# 4_waffling60-SE_periferals.net
KiCad netlist of a schematic drawn in Altium Designer
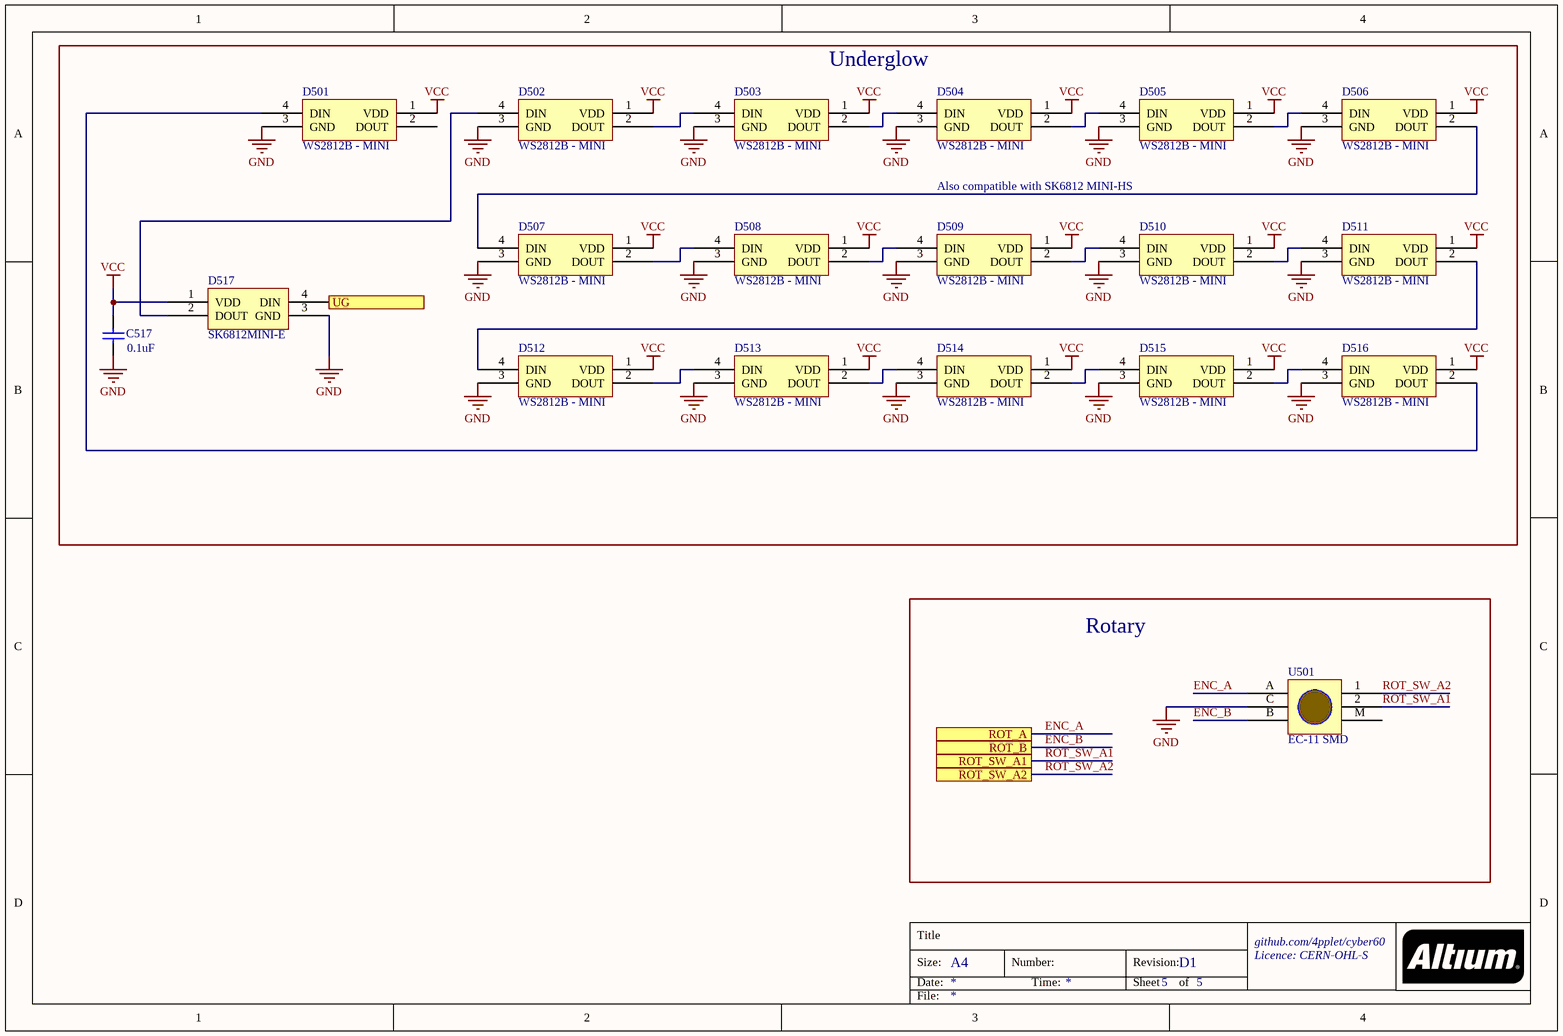
[diagram p0: 4_waffling60-SE_periferals.SchDoc]

(export (version "E")
  (design (tool "Eeschema 10.0.6"))
  (components
    (comp (ref "C517")
      (value "0.1uF")
      (footprint "C0603[1608]")
      (description "Capacitor")
      (fields (field (name "LCSC PART #") "C14663") (field (name "MRF.PART") "CC0603KRX7R9BB104"))
      (libsource (lib "Miscellaneous Devices") (part "Cap"))
    )
    (comp (ref "D501")
      (value "WS2812B - MINI")
      (footprint "WS2812B - 2020")
      (fields (field (name "LCSC PART #") "C965556") (field (name "MRF.PART") "WS2812C-2020"))
      (libsource (lib "Keebs") (part "WS2812B"))
    )
    (comp (ref "D502")
      (value "WS2812B - MINI")
      (footprint "WS2812B - 2020")
      (fields (field (name "LCSC PART #") "C965556") (field (name "MRF.PART") "WS2812C-2020"))
      (libsource (lib "Keebs") (part "WS2812B"))
    )
    (comp (ref "D503")
      (value "WS2812B - MINI")
      (footprint "WS2812B - 2020")
      (fields (field (name "LCSC PART #") "C965556") (field (name "MRF.PART") "WS2812C-2020"))
      (libsource (lib "Keebs") (part "WS2812B"))
    )
    (comp (ref "D504")
      (value "WS2812B - MINI")
      (footprint "WS2812B - 2020")
      (fields (field (name "LCSC PART #") "C965556") (field (name "MRF.PART") "WS2812C-2020"))
      (libsource (lib "Keebs") (part "WS2812B"))
    )
    (comp (ref "D505")
      (value "WS2812B - MINI")
      (footprint "WS2812B - 2020")
      (fields (field (name "LCSC PART #") "C965556") (field (name "MRF.PART") "WS2812C-2020"))
      (libsource (lib "Keebs") (part "WS2812B"))
    )
    (comp (ref "D506")
      (value "WS2812B - MINI")
      (footprint "WS2812B - 2020")
      (fields (field (name "LCSC PART #") "C965556") (field (name "MRF.PART") "WS2812C-2020"))
      (libsource (lib "Keebs") (part "WS2812B"))
    )
    (comp (ref "D507")
      (value "WS2812B - MINI")
      (footprint "WS2812B - 2020")
      (fields (field (name "LCSC PART #") "C965556") (field (name "MRF.PART") "WS2812C-2020"))
      (libsource (lib "Keebs") (part "WS2812B"))
    )
    (comp (ref "D508")
      (value "WS2812B - MINI")
      (footprint "WS2812B - 2020")
      (fields (field (name "LCSC PART #") "C965556") (field (name "MRF.PART") "WS2812C-2020"))
      (libsource (lib "Keebs") (part "WS2812B"))
    )
    (comp (ref "D509")
      (value "WS2812B - MINI")
      (footprint "WS2812B - 2020")
      (fields (field (name "LCSC PART #") "C965556") (field (name "MRF.PART") "WS2812C-2020"))
      (libsource (lib "Keebs") (part "WS2812B"))
    )
    (comp (ref "D510")
      (value "WS2812B - MINI")
      (footprint "WS2812B - 2020")
      (fields (field (name "LCSC PART #") "C965556") (field (name "MRF.PART") "WS2812C-2020"))
      (libsource (lib "Keebs") (part "WS2812B"))
    )
    (comp (ref "D511")
      (value "WS2812B - MINI")
      (footprint "WS2812B - 2020")
      (fields (field (name "LCSC PART #") "C965556") (field (name "MRF.PART") "WS2812C-2020"))
      (libsource (lib "Keebs") (part "WS2812B"))
    )
    (comp (ref "D512")
      (value "WS2812B - MINI")
      (footprint "WS2812B - 2020")
      (fields (field (name "LCSC PART #") "C965556") (field (name "MRF.PART") "WS2812C-2020"))
      (libsource (lib "Keebs") (part "WS2812B"))
    )
    (comp (ref "D513")
      (value "WS2812B - MINI")
      (footprint "WS2812B - 2020")
      (fields (field (name "LCSC PART #") "C965556") (field (name "MRF.PART") "WS2812C-2020"))
      (libsource (lib "Keebs") (part "WS2812B"))
    )
    (comp (ref "D514")
      (value "WS2812B - MINI")
      (footprint "WS2812B - 2020")
      (fields (field (name "LCSC PART #") "C965556") (field (name "MRF.PART") "WS2812C-2020"))
      (libsource (lib "Keebs") (part "WS2812B"))
    )
    (comp (ref "D515")
      (value "WS2812B - MINI")
      (footprint "WS2812B - 2020")
      (fields (field (name "LCSC PART #") "C965556") (field (name "MRF.PART") "WS2812C-2020"))
      (libsource (lib "Keebs") (part "WS2812B"))
    )
    (comp (ref "D516")
      (value "WS2812B - MINI")
      (footprint "WS2812B - 2020")
      (fields (field (name "LCSC PART #") "C965556") (field (name "MRF.PART") "WS2812C-2020"))
      (libsource (lib "Keebs") (part "WS2812B"))
    )
    (comp (ref "D517")
      (value "SK6812MINI-E")
      (footprint "SK6812MINI-E - shaped")
      (fields (field (name "LCSC PART #") "C524051") (field (name "MRF.PART") "DY-S352818/RGBC/6812-2T"))
      (libsource (lib "Keebs") (part "SK6812MINI-E"))
    )
    (comp (ref "U501") (value "EC-11 SMD") (footprint "EC11-SMD") (libsource (lib "Keebs") (part "EC-11")))
  )
  (nets
    (net (code "1") (name "/ENC_A") (class "Default")
      (node (ref "U501") (pin "A") (pinfunction "B_A") (pintype "passive"))
    )
    (net (code "2") (name "/ENC_B") (class "Default")
      (node (ref "U501") (pin "B") (pinfunction "B_B") (pintype "passive"))
    )
    (net (code "3") (name "/ROT_SW_A1") (class "Default")
      (node (ref "U501") (pin "2") (pinfunction "2_2") (pintype "passive"))
    )
    (net (code "4") (name "/ROT_SW_A2") (class "Default")
      (node (ref "U501") (pin "1") (pinfunction "1_1") (pintype "passive"))
    )
    (net (code "5") (name "/UG") (class "Default")
      (node (ref "D517") (pin "4") (pinfunction "DIN_4") (pintype "passive"))
    )
    (net (code "6") (name "GND") (class "Default")
      (node (ref "C517") (pin "1") (pinfunction "1_1") (pintype "passive"))
      (node (ref "D501") (pin "3") (pinfunction "GND_3") (pintype "passive"))
      (node (ref "D502") (pin "3") (pinfunction "GND_3") (pintype "passive"))
      (node (ref "D503") (pin "3") (pinfunction "GND_3") (pintype "passive"))
      (node (ref "D504") (pin "3") (pinfunction "GND_3") (pintype "passive"))
      (node (ref "D505") (pin "3") (pinfunction "GND_3") (pintype "passive"))
      (node (ref "D506") (pin "3") (pinfunction "GND_3") (pintype "passive"))
      (node (ref "D507") (pin "3") (pinfunction "GND_3") (pintype "passive"))
      (node (ref "D508") (pin "3") (pinfunction "GND_3") (pintype "passive"))
      (node (ref "D509") (pin "3") (pinfunction "GND_3") (pintype "passive"))
      (node (ref "D510") (pin "3") (pinfunction "GND_3") (pintype "passive"))
      (node (ref "D511") (pin "3") (pinfunction "GND_3") (pintype "passive"))
      (node (ref "D512") (pin "3") (pinfunction "GND_3") (pintype "passive"))
      (node (ref "D513") (pin "3") (pinfunction "GND_3") (pintype "passive"))
      (node (ref "D514") (pin "3") (pinfunction "GND_3") (pintype "passive"))
      (node (ref "D515") (pin "3") (pinfunction "GND_3") (pintype "passive"))
      (node (ref "D516") (pin "3") (pinfunction "GND_3") (pintype "passive"))
      (node (ref "D517") (pin "3") (pinfunction "GND_3") (pintype "passive"))
      (node (ref "U501") (pin "C") (pinfunction "C_C") (pintype "passive"))
    )
    (net (code "7") (name "Net-(D501-DIN)") (class "Default")
      (node (ref "D501") (pin "4") (pinfunction "DIN_4") (pintype "passive"))
      (node (ref "D516") (pin "2") (pinfunction "DOUT_2") (pintype "passive"))
    )
    (net (code "8") (name "Net-(D502-DIN)") (class "Default")
      (node (ref "D502") (pin "4") (pinfunction "DIN_4") (pintype "passive"))
      (node (ref "D517") (pin "2") (pinfunction "DOUT_2") (pintype "passive"))
    )
    (net (code "9") (name "Net-(D502-DOUT)") (class "Default")
      (node (ref "D502") (pin "2") (pinfunction "DOUT_2") (pintype "passive"))
      (node (ref "D503") (pin "4") (pinfunction "DIN_4") (pintype "passive"))
    )
    (net (code "10") (name "Net-(D503-DOUT)") (class "Default")
      (node (ref "D503") (pin "2") (pinfunction "DOUT_2") (pintype "passive"))
      (node (ref "D504") (pin "4") (pinfunction "DIN_4") (pintype "passive"))
    )
    (net (code "11") (name "Net-(D504-DOUT)") (class "Default")
      (node (ref "D504") (pin "2") (pinfunction "DOUT_2") (pintype "passive"))
      (node (ref "D505") (pin "4") (pinfunction "DIN_4") (pintype "passive"))
    )
    (net (code "12") (name "Net-(D505-DOUT)") (class "Default")
      (node (ref "D505") (pin "2") (pinfunction "DOUT_2") (pintype "passive"))
      (node (ref "D506") (pin "4") (pinfunction "DIN_4") (pintype "passive"))
    )
    (net (code "13") (name "Net-(D506-DOUT)") (class "Default")
      (node (ref "D506") (pin "2") (pinfunction "DOUT_2") (pintype "passive"))
      (node (ref "D507") (pin "4") (pinfunction "DIN_4") (pintype "passive"))
    )
    (net (code "14") (name "Net-(D507-DOUT)") (class "Default")
      (node (ref "D507") (pin "2") (pinfunction "DOUT_2") (pintype "passive"))
      (node (ref "D508") (pin "4") (pinfunction "DIN_4") (pintype "passive"))
    )
    (net (code "15") (name "Net-(D508-DOUT)") (class "Default")
      (node (ref "D508") (pin "2") (pinfunction "DOUT_2") (pintype "passive"))
      (node (ref "D509") (pin "4") (pinfunction "DIN_4") (pintype "passive"))
    )
    (net (code "16") (name "Net-(D509-DOUT)") (class "Default")
      (node (ref "D509") (pin "2") (pinfunction "DOUT_2") (pintype "passive"))
      (node (ref "D510") (pin "4") (pinfunction "DIN_4") (pintype "passive"))
    )
    (net (code "17") (name "Net-(D510-DOUT)") (class "Default")
      (node (ref "D510") (pin "2") (pinfunction "DOUT_2") (pintype "passive"))
      (node (ref "D511") (pin "4") (pinfunction "DIN_4") (pintype "passive"))
    )
    (net (code "18") (name "Net-(D511-DOUT)") (class "Default")
      (node (ref "D511") (pin "2") (pinfunction "DOUT_2") (pintype "passive"))
      (node (ref "D512") (pin "4") (pinfunction "DIN_4") (pintype "passive"))
    )
    (net (code "19") (name "Net-(D512-DOUT)") (class "Default")
      (node (ref "D512") (pin "2") (pinfunction "DOUT_2") (pintype "passive"))
      (node (ref "D513") (pin "4") (pinfunction "DIN_4") (pintype "passive"))
    )
    (net (code "20") (name "Net-(D513-DOUT)") (class "Default")
      (node (ref "D513") (pin "2") (pinfunction "DOUT_2") (pintype "passive"))
      (node (ref "D514") (pin "4") (pinfunction "DIN_4") (pintype "passive"))
    )
    (net (code "21") (name "Net-(D514-DOUT)") (class "Default")
      (node (ref "D514") (pin "2") (pinfunction "DOUT_2") (pintype "passive"))
      (node (ref "D515") (pin "4") (pinfunction "DIN_4") (pintype "passive"))
    )
    (net (code "22") (name "Net-(D515-DOUT)") (class "Default")
      (node (ref "D515") (pin "2") (pinfunction "DOUT_2") (pintype "passive"))
      (node (ref "D516") (pin "4") (pinfunction "DIN_4") (pintype "passive"))
    )
    (net (code "23") (name "VCC") (class "Default")
      (node (ref "C517") (pin "2") (pinfunction "2_2") (pintype "passive"))
      (node (ref "D501") (pin "1") (pinfunction "VDD_1") (pintype "passive"))
      (node (ref "D502") (pin "1") (pinfunction "VDD_1") (pintype "passive"))
      (node (ref "D503") (pin "1") (pinfunction "VDD_1") (pintype "passive"))
      (node (ref "D504") (pin "1") (pinfunction "VDD_1") (pintype "passive"))
      (node (ref "D505") (pin "1") (pinfunction "VDD_1") (pintype "passive"))
      (node (ref "D506") (pin "1") (pinfunction "VDD_1") (pintype "passive"))
      (node (ref "D507") (pin "1") (pinfunction "VDD_1") (pintype "passive"))
      (node (ref "D508") (pin "1") (pinfunction "VDD_1") (pintype "passive"))
      (node (ref "D509") (pin "1") (pinfunction "VDD_1") (pintype "passive"))
      (node (ref "D510") (pin "1") (pinfunction "VDD_1") (pintype "passive"))
      (node (ref "D511") (pin "1") (pinfunction "VDD_1") (pintype "passive"))
      (node (ref "D512") (pin "1") (pinfunction "VDD_1") (pintype "passive"))
      (node (ref "D513") (pin "1") (pinfunction "VDD_1") (pintype "passive"))
      (node (ref "D514") (pin "1") (pinfunction "VDD_1") (pintype "passive"))
      (node (ref "D515") (pin "1") (pinfunction "VDD_1") (pintype "passive"))
      (node (ref "D516") (pin "1") (pinfunction "VDD_1") (pintype "passive"))
      (node (ref "D517") (pin "1") (pinfunction "VDD_1") (pintype "passive"))
    )
    (net (code "24") (name "unconnected-(D501-DOUT-Pad2)") (class "Default")
      (node (ref "D501") (pin "2") (pinfunction "DOUT_2") (pintype "passive"))
    )
    (net (code "25") (name "unconnected-(U501-PadM)") (class "Default")
      (node (ref "U501") (pin "M") (pinfunction "M_M") (pintype "passive"))
    )
  )
)
